# Aux_Board_V5_1.net
KiCad netlist of a schematic drawn in EAGLE
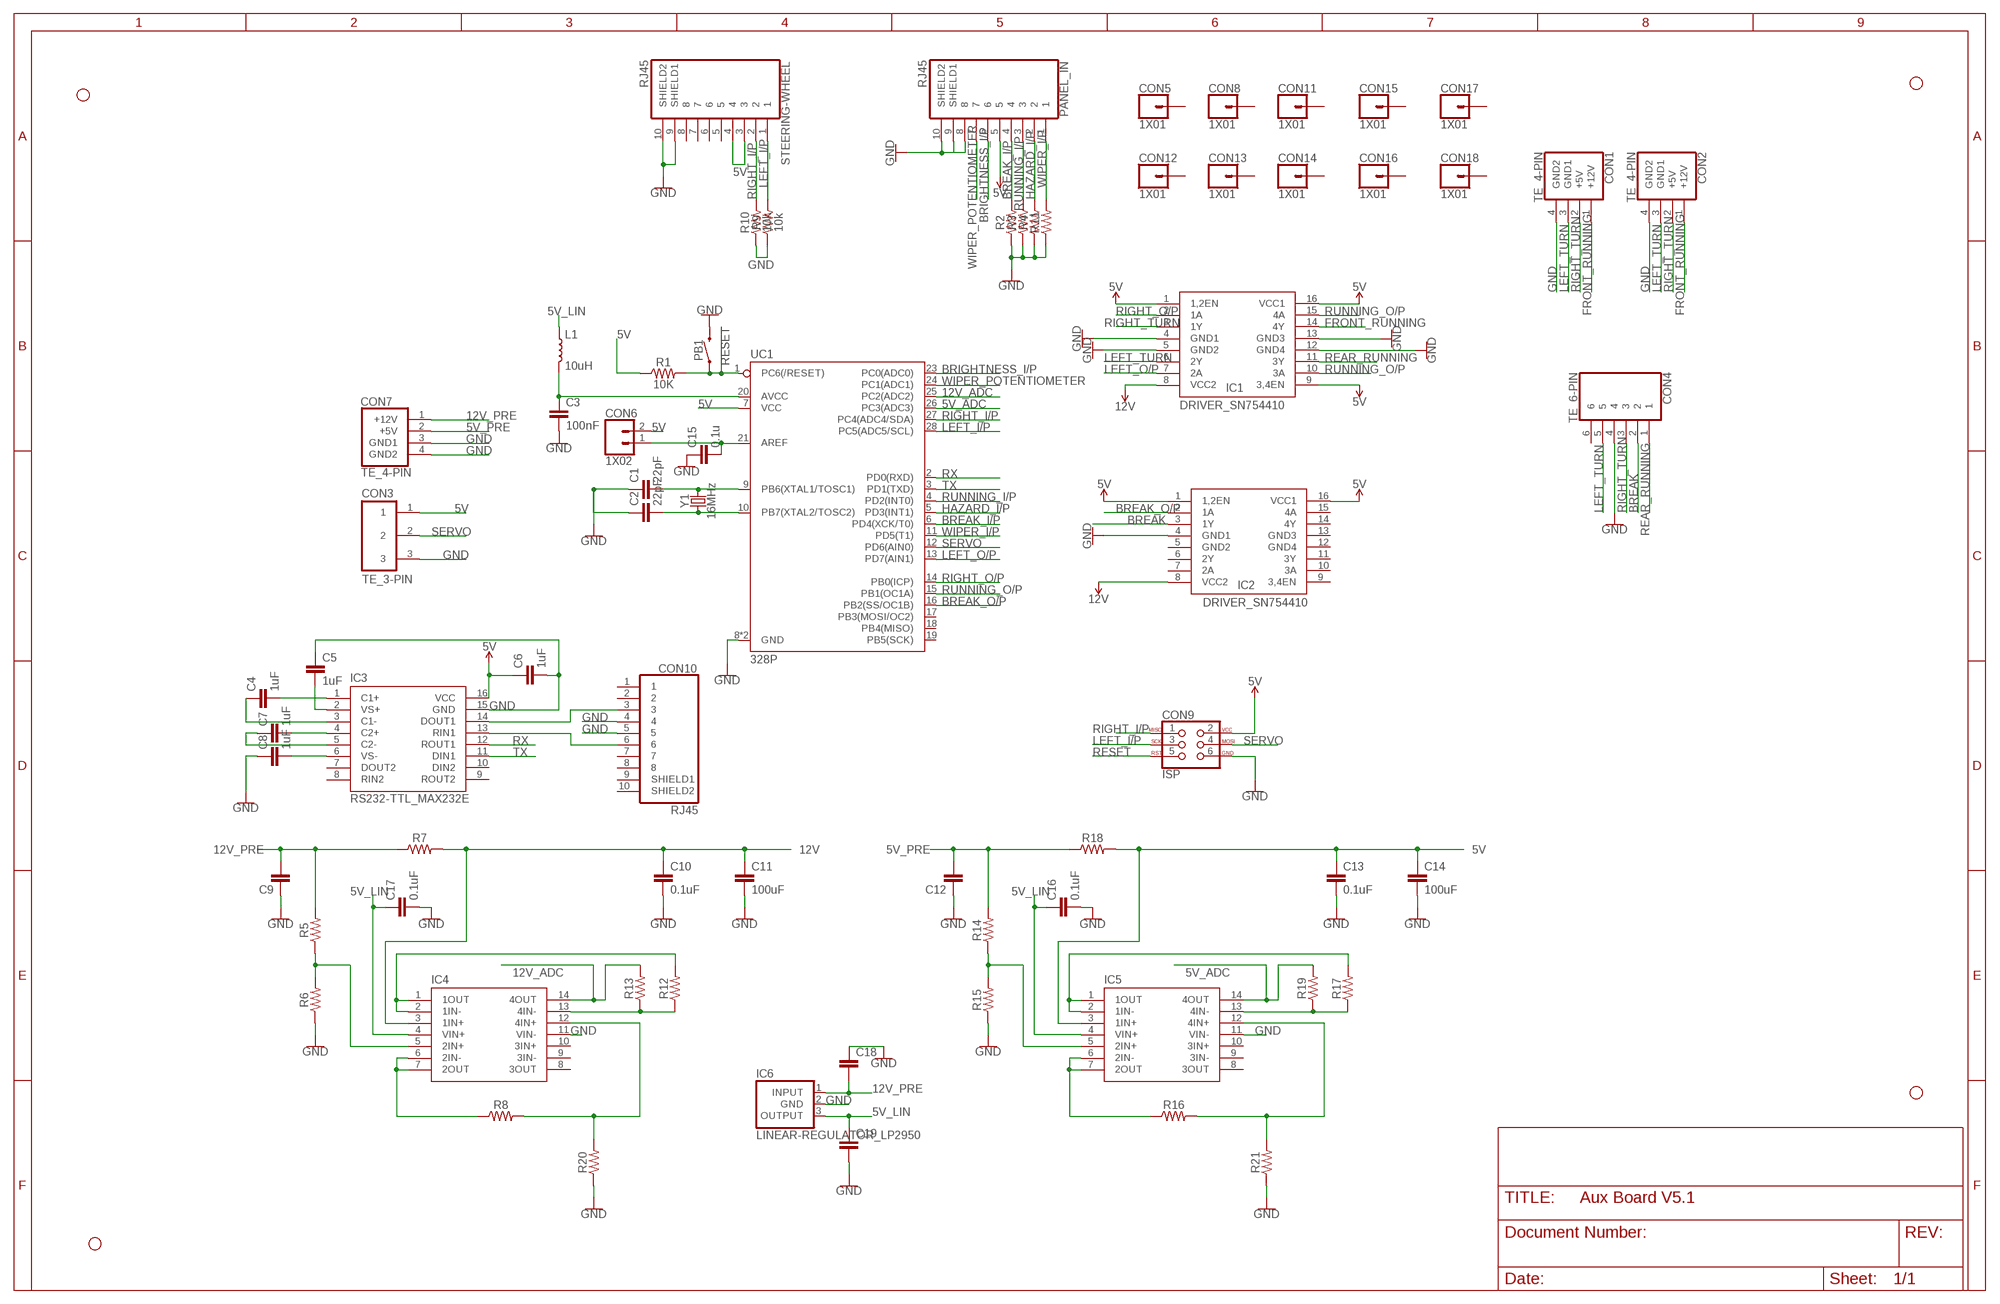
[diagram p0: schematic, sheet 1]

(export (version "E")
  (design (tool "Eeschema 10.0.6"))
  (components
    (comp (ref "C1")
      (value "22pF")
      (footprint "eagle-import:0805")
      (libsource (lib "eagle-import") (part "CAPACITOR_0805"))
    )
    (comp (ref "C2")
      (value "22pF")
      (footprint "eagle-import:0805")
      (libsource (lib "eagle-import") (part "CAPACITOR_0805"))
    )
    (comp (ref "C3")
      (value "100nF")
      (footprint "eagle-import:0805")
      (libsource (lib "eagle-import") (part "CAPACITOR_0805"))
    )
    (comp (ref "C4")
      (value "1uF")
      (footprint "eagle-import:0805")
      (libsource (lib "eagle-import") (part "CAPACITOR_0805"))
    )
    (comp (ref "C5")
      (value "1uF")
      (footprint "eagle-import:0805")
      (libsource (lib "eagle-import") (part "CAPACITOR_0805"))
    )
    (comp (ref "C6")
      (value "1uF")
      (footprint "eagle-import:0805")
      (libsource (lib "eagle-import") (part "CAPACITOR_0805"))
    )
    (comp (ref "C7")
      (value "1uF")
      (footprint "eagle-import:0805")
      (libsource (lib "eagle-import") (part "CAPACITOR_0805"))
    )
    (comp (ref "C8")
      (value "1uF")
      (footprint "eagle-import:0805")
      (libsource (lib "eagle-import") (part "CAPACITOR_0805"))
    )
    (comp (ref "C9")
      (value "CAPACITOR_0805")
      (footprint "eagle-import:0805")
      (libsource (lib "eagle-import") (part "CAPACITOR_0805"))
    )
    (comp (ref "C10")
      (value "0.1uF")
      (footprint "eagle-import:0805")
      (libsource (lib "eagle-import") (part "CAPACITOR_0805"))
    )
    (comp (ref "C11")
      (value "100uF")
      (footprint "eagle-import:0805")
      (libsource (lib "eagle-import") (part "CAPACITOR_0805"))
    )
    (comp (ref "C12")
      (value "CAPACITOR_0805")
      (footprint "eagle-import:0805")
      (libsource (lib "eagle-import") (part "CAPACITOR_0805"))
    )
    (comp (ref "C13")
      (value "0.1uF")
      (footprint "eagle-import:0805")
      (libsource (lib "eagle-import") (part "CAPACITOR_0805"))
    )
    (comp (ref "C14")
      (value "100uF")
      (footprint "eagle-import:0805")
      (libsource (lib "eagle-import") (part "CAPACITOR_0805"))
    )
    (comp (ref "C15")
      (value "0.1u")
      (footprint "eagle-import:0805")
      (libsource (lib "eagle-import") (part "CAPACITOR_0805"))
    )
    (comp (ref "C16")
      (value "0.1uF")
      (footprint "eagle-import:0805")
      (libsource (lib "eagle-import") (part "CAPACITOR_0805"))
    )
    (comp (ref "C17")
      (value "0.1uF")
      (footprint "eagle-import:0805")
      (libsource (lib "eagle-import") (part "CAPACITOR_0805"))
    )
    (comp (ref "C18")
      (value "CAPACITOR_0805")
      (footprint "eagle-import:0805")
      (libsource (lib "eagle-import") (part "CAPACITOR_0805"))
    )
    (comp (ref "C19")
      (value "CAPACITOR_0805")
      (footprint "eagle-import:0805")
      (libsource (lib "eagle-import") (part "CAPACITOR_0805"))
    )
    (comp (ref "CON1")
      (value "TE_4-PIN")
      (footprint "eagle-import:TE_4-PIN")
      (libsource (lib "eagle-import") (part "TE_4-PIN"))
    )
    (comp (ref "CON2")
      (value "TE_4-PIN")
      (footprint "eagle-import:TE_4-PIN")
      (libsource (lib "eagle-import") (part "TE_4-PIN"))
    )
    (comp (ref "CON3")
      (value "TE_3-PIN")
      (footprint "eagle-import:TE_3-PIN")
      (libsource (lib "eagle-import") (part "TE_3-PIN"))
    )
    (comp (ref "CON4")
      (value "TE_6-PIN")
      (footprint "eagle-import:TE_6-PIN")
      (libsource (lib "eagle-import") (part "TE_6-PIN"))
    )
    (comp (ref "CON5")
      (value "1X01")
      (footprint "eagle-import:1X01")
      (libsource (lib "eagle-import") (part "1X01"))
    )
    (comp (ref "CON6")
      (value "1X02")
      (footprint "eagle-import:1X02")
      (libsource (lib "eagle-import") (part "1X02"))
    )
    (comp (ref "CON7")
      (value "TE_4-PIN")
      (footprint "eagle-import:TE_4-PIN")
      (libsource (lib "eagle-import") (part "TE_4-PIN"))
    )
    (comp (ref "CON8")
      (value "1X01")
      (footprint "eagle-import:1X01")
      (libsource (lib "eagle-import") (part "1X01"))
    )
    (comp (ref "CON9")
      (value "ISP")
      (footprint "eagle-import:ISP_CONNECTOR")
      (libsource (lib "eagle-import") (part "ISP"))
    )
    (comp (ref "CON10")
      (value "RJ45")
      (footprint "eagle-import:RJ45")
      (libsource (lib "eagle-import") (part "RJ45"))
    )
    (comp (ref "CON11")
      (value "1X01")
      (footprint "eagle-import:1X01")
      (libsource (lib "eagle-import") (part "1X01"))
    )
    (comp (ref "CON12")
      (value "1X01")
      (footprint "eagle-import:1X01")
      (libsource (lib "eagle-import") (part "1X01"))
    )
    (comp (ref "CON13")
      (value "1X01")
      (footprint "eagle-import:1X01")
      (libsource (lib "eagle-import") (part "1X01"))
    )
    (comp (ref "CON14")
      (value "1X01")
      (footprint "eagle-import:1X01")
      (libsource (lib "eagle-import") (part "1X01"))
    )
    (comp (ref "CON15")
      (value "1X01")
      (footprint "eagle-import:1X01")
      (libsource (lib "eagle-import") (part "1X01"))
    )
    (comp (ref "CON16")
      (value "1X01")
      (footprint "eagle-import:1X01")
      (libsource (lib "eagle-import") (part "1X01"))
    )
    (comp (ref "CON17")
      (value "1X01")
      (footprint "eagle-import:1X01")
      (libsource (lib "eagle-import") (part "1X01"))
    )
    (comp (ref "CON18")
      (value "1X01")
      (footprint "eagle-import:1X01")
      (libsource (lib "eagle-import") (part "1X01"))
    )
    (comp (ref "H1")
      (value "STAND-OFF")
      (footprint "eagle-import:STAND-OFF")
      (libsource (lib "eagle-import") (part "STAND-OFF"))
    )
    (comp (ref "H2")
      (value "STAND-OFF")
      (footprint "eagle-import:STAND-OFF")
      (libsource (lib "eagle-import") (part "STAND-OFF"))
    )
    (comp (ref "H3")
      (value "STAND-OFF")
      (footprint "eagle-import:STAND-OFF")
      (libsource (lib "eagle-import") (part "STAND-OFF"))
    )
    (comp (ref "H4")
      (value "STAND-OFF")
      (footprint "eagle-import:STAND-OFF")
      (libsource (lib "eagle-import") (part "STAND-OFF"))
    )
    (comp (ref "IC1")
      (value "DRIVER_SN754410")
      (footprint "eagle-import:DIP16")
      (libsource (lib "eagle-import") (part "DRIVER_SN754410"))
    )
    (comp (ref "IC2")
      (value "DRIVER_SN754410")
      (footprint "eagle-import:DIP16")
      (libsource (lib "eagle-import") (part "DRIVER_SN754410"))
    )
    (comp (ref "IC3")
      (value "RS232-TTL_MAX232E")
      (footprint "eagle-import:DIP16")
      (libsource (lib "eagle-import") (part "RS232-TTL_MAX232E"))
    )
    (comp (ref "IC4")
      (value "OP-AMP_QUAD")
      (footprint "eagle-import:DIP14")
      (libsource (lib "eagle-import") (part "OP-AMP_QUAD"))
    )
    (comp (ref "IC5")
      (value "OP-AMP_QUAD")
      (footprint "eagle-import:DIP14")
      (libsource (lib "eagle-import") (part "OP-AMP_QUAD"))
    )
    (comp (ref "IC6")
      (value "LINEAR-REGULATOR_LP2950")
      (footprint "eagle-import:TO92")
      (libsource (lib "eagle-import") (part "LINEAR-REGULATOR_LP2950"))
    )
    (comp (ref "L1")
      (value "10uH")
      (footprint "eagle-import:0805")
      (libsource (lib "eagle-import") (part "INDUCTOR_0805"))
    )
    (comp (ref "PANEL_IN")
      (value "RJ45")
      (footprint "eagle-import:RJ45")
      (libsource (lib "eagle-import") (part "RJ45"))
    )
    (comp (ref "PB1")
      (value "PUSHBUTTON")
      (footprint "eagle-import:PUSHBUTTON")
      (libsource (lib "eagle-import") (part "PUSHBUTTON"))
    )
    (comp (ref "R1")
      (value "10K")
      (footprint "eagle-import:0805")
      (libsource (lib "eagle-import") (part "RESISTOR_0805"))
    )
    (comp (ref "R2")
      (value "RESISTOR_0805")
      (footprint "eagle-import:0805")
      (libsource (lib "eagle-import") (part "RESISTOR_0805"))
    )
    (comp (ref "R3")
      (value "RESISTOR_0805")
      (footprint "eagle-import:0805")
      (libsource (lib "eagle-import") (part "RESISTOR_0805"))
    )
    (comp (ref "R4")
      (value "RESISTOR_0805")
      (footprint "eagle-import:0805")
      (libsource (lib "eagle-import") (part "RESISTOR_0805"))
    )
    (comp (ref "R5")
      (value "RESISTOR_0805")
      (footprint "eagle-import:0805")
      (libsource (lib "eagle-import") (part "RESISTOR_0805"))
    )
    (comp (ref "R6")
      (value "RESISTOR_0805")
      (footprint "eagle-import:0805")
      (libsource (lib "eagle-import") (part "RESISTOR_0805"))
    )
    (comp (ref "R7")
      (value "RESISTOR_1210")
      (footprint "eagle-import:1210")
      (libsource (lib "eagle-import") (part "RESISTOR_1210"))
    )
    (comp (ref "R8")
      (value "RESISTOR_0805")
      (footprint "eagle-import:0805")
      (libsource (lib "eagle-import") (part "RESISTOR_0805"))
    )
    (comp (ref "R9")
      (value "10k")
      (footprint "eagle-import:0805")
      (libsource (lib "eagle-import") (part "RESISTOR_0805"))
    )
    (comp (ref "R10")
      (value "10k")
      (footprint "eagle-import:0805")
      (libsource (lib "eagle-import") (part "RESISTOR_0805"))
    )
    (comp (ref "R11")
      (value "RESISTOR_0805")
      (footprint "eagle-import:0805")
      (libsource (lib "eagle-import") (part "RESISTOR_0805"))
    )
    (comp (ref "R12")
      (value "RESISTOR_0805")
      (footprint "eagle-import:0805")
      (libsource (lib "eagle-import") (part "RESISTOR_0805"))
    )
    (comp (ref "R13")
      (value "RESISTOR_0805")
      (footprint "eagle-import:0805")
      (libsource (lib "eagle-import") (part "RESISTOR_0805"))
    )
    (comp (ref "R14")
      (value "RESISTOR_0805")
      (footprint "eagle-import:0805")
      (libsource (lib "eagle-import") (part "RESISTOR_0805"))
    )
    (comp (ref "R15")
      (value "RESISTOR_0805")
      (footprint "eagle-import:0805")
      (libsource (lib "eagle-import") (part "RESISTOR_0805"))
    )
    (comp (ref "R16")
      (value "RESISTOR_0805")
      (footprint "eagle-import:0805")
      (libsource (lib "eagle-import") (part "RESISTOR_0805"))
    )
    (comp (ref "R17")
      (value "RESISTOR_0805")
      (footprint "eagle-import:0805")
      (libsource (lib "eagle-import") (part "RESISTOR_0805"))
    )
    (comp (ref "R18")
      (value "RESISTOR_1210")
      (footprint "eagle-import:1210")
      (libsource (lib "eagle-import") (part "RESISTOR_1210"))
    )
    (comp (ref "R19")
      (value "RESISTOR_0805")
      (footprint "eagle-import:0805")
      (libsource (lib "eagle-import") (part "RESISTOR_0805"))
    )
    (comp (ref "R20")
      (value "RESISTOR_0805")
      (footprint "eagle-import:0805")
      (libsource (lib "eagle-import") (part "RESISTOR_0805"))
    )
    (comp (ref "R21")
      (value "RESISTOR_0805")
      (footprint "eagle-import:0805")
      (libsource (lib "eagle-import") (part "RESISTOR_0805"))
    )
    (comp (ref "STEERING-WHEEL")
      (value "RJ45")
      (footprint "eagle-import:RJ45")
      (libsource (lib "eagle-import") (part "RJ45"))
    )
    (comp (ref "UC1")
      (value "328P")
      (footprint "eagle-import:DIP28")
      (libsource (lib "eagle-import") (part "ATMEGA328P_DIP28"))
    )
    (comp (ref "Y1")
      (value "16MHz")
      (footprint "eagle-import:HC49US")
      (libsource (lib "eagle-import") (part "CRYSTAL-16MHZPTH-HC49US"))
    )
  )
  (nets
    (net (code "1") (name "/5V_ADC") (class "Default")
      (node (ref "IC5") (pin "14") (pinfunction "4OUT_14") (pintype "bidirectional"))
      (node (ref "R19") (pin "2") (pinfunction "2_2") (pintype "passive"))
      (node (ref "UC1") (pin "26") (pinfunction "PC3(ADC3)_26") (pintype "bidirectional"))
    )
    (net (code "2") (name "/5V_LIN") (class "Default")
      (node (ref "C16") (pin "1") (pinfunction "1_1") (pintype "passive"))
      (node (ref "C17") (pin "1") (pinfunction "1_1") (pintype "passive"))
      (node (ref "C19") (pin "1") (pinfunction "1_1") (pintype "passive"))
      (node (ref "IC4") (pin "4") (pinfunction "VIN+_4") (pintype "bidirectional"))
      (node (ref "IC5") (pin "4") (pinfunction "VIN+_4") (pintype "bidirectional"))
      (node (ref "IC6") (pin "3") (pinfunction "OUTPUT_3") (pintype "bidirectional"))
      (node (ref "L1") (pin "1") (pinfunction "1_1") (pintype "passive"))
    )
    (net (code "3") (name "/5V_PRE") (class "Default")
      (node (ref "C12") (pin "2") (pinfunction "2_2") (pintype "passive"))
      (node (ref "CON7") (pin "2") (pinfunction "+5V_2") (pintype "passive"))
      (node (ref "R14") (pin "2") (pinfunction "2_2") (pintype "passive"))
      (node (ref "R18") (pin "1") (pinfunction "1_1") (pintype "passive"))
    )
    (net (code "4") (name "/12V_ADC") (class "Default")
      (node (ref "IC4") (pin "14") (pinfunction "4OUT_14") (pintype "bidirectional"))
      (node (ref "R13") (pin "2") (pinfunction "2_2") (pintype "passive"))
      (node (ref "UC1") (pin "25") (pinfunction "PC2(ADC2)_25") (pintype "bidirectional"))
    )
    (net (code "5") (name "/12V_PRE") (class "Default")
      (node (ref "C18") (pin "2") (pinfunction "2_2") (pintype "passive"))
      (node (ref "C9") (pin "2") (pinfunction "2_2") (pintype "passive"))
      (node (ref "CON7") (pin "1") (pinfunction "+12V_1") (pintype "passive"))
      (node (ref "IC6") (pin "1") (pinfunction "INPUT_1") (pintype "bidirectional"))
      (node (ref "R5") (pin "2") (pinfunction "2_2") (pintype "passive"))
      (node (ref "R7") (pin "1") (pinfunction "1_1") (pintype "passive"))
    )
    (net (code "6") (name "/BREAK") (class "Default")
      (node (ref "CON4") (pin "2") (pinfunction "2_2") (pintype "passive"))
      (node (ref "IC2") (pin "3") (pinfunction "1Y_3") (pintype "bidirectional"))
    )
    (net (code "7") (name "/BREAK_I{slash}P") (class "Default")
      (node (ref "PANEL_IN") (pin "4") (pinfunction "4_4") (pintype "passive"))
      (node (ref "R2") (pin "2") (pinfunction "2_2") (pintype "passive"))
      (node (ref "UC1") (pin "6") (pinfunction "PD4(XCK/T0)_6") (pintype "bidirectional"))
    )
    (net (code "8") (name "/BREAK_O{slash}P") (class "Default")
      (node (ref "IC2") (pin "2") (pinfunction "1A_2") (pintype "bidirectional"))
      (node (ref "UC1") (pin "16") (pinfunction "PB2(SS/OC1B)_16") (pintype "bidirectional"))
    )
    (net (code "9") (name "/BRIGHTNESS_I{slash}P") (class "Default")
      (node (ref "PANEL_IN") (pin "6") (pinfunction "6_6") (pintype "passive"))
      (node (ref "UC1") (pin "23") (pinfunction "PC0(ADC0)_23") (pintype "bidirectional"))
    )
    (net (code "10") (name "/FRONT_RUNNING") (class "Default")
      (node (ref "CON1") (pin "1") (pinfunction "+12V_1") (pintype "passive"))
      (node (ref "CON2") (pin "1") (pinfunction "+12V_1") (pintype "passive"))
      (node (ref "IC1") (pin "14") (pinfunction "4Y_14") (pintype "bidirectional"))
    )
    (net (code "11") (name "/HAZARD_I{slash}P") (class "Default")
      (node (ref "PANEL_IN") (pin "2") (pinfunction "2_2") (pintype "passive"))
      (node (ref "R4") (pin "2") (pinfunction "2_2") (pintype "passive"))
      (node (ref "UC1") (pin "5") (pinfunction "PD3(INT1)_5") (pintype "bidirectional"))
    )
    (net (code "12") (name "/LEFT_I{slash}P") (class "Default")
      (node (ref "CON9") (pin "3") (pinfunction "3_3") (pintype "passive"))
      (node (ref "R9") (pin "2") (pinfunction "2_2") (pintype "passive"))
      (node (ref "STEERING-WHEEL") (pin "1") (pinfunction "1_1") (pintype "passive"))
      (node (ref "UC1") (pin "28") (pinfunction "PC5(ADC5/SCL)_28") (pintype "bidirectional"))
    )
    (net (code "13") (name "/LEFT_O{slash}P") (class "Default")
      (node (ref "IC1") (pin "7") (pinfunction "2A_7") (pintype "bidirectional"))
      (node (ref "UC1") (pin "13") (pinfunction "PD7(AIN1)_13") (pintype "bidirectional"))
    )
    (net (code "14") (name "/LEFT_TURN") (class "Default")
      (node (ref "CON1") (pin "3") (pinfunction "GND1_3") (pintype "passive"))
      (node (ref "CON2") (pin "3") (pinfunction "GND1_3") (pintype "passive"))
      (node (ref "CON4") (pin "5") (pinfunction "5_5") (pintype "passive"))
      (node (ref "IC1") (pin "6") (pinfunction "2Y_6") (pintype "bidirectional"))
    )
    (net (code "15") (name "/REAR_RUNNING") (class "Default")
      (node (ref "CON4") (pin "1") (pinfunction "1_1") (pintype "passive"))
      (node (ref "IC1") (pin "11") (pinfunction "3Y_11") (pintype "bidirectional"))
    )
    (net (code "16") (name "/RESET") (class "Default")
      (node (ref "CON9") (pin "5") (pinfunction "5_5") (pintype "passive"))
      (node (ref "PB1") (pin "1") (pinfunction "1_1") (pintype "passive"))
      (node (ref "PB1") (pin "2") (pinfunction "1_2") (pintype "passive"))
      (node (ref "R1") (pin "2") (pinfunction "2_2") (pintype "passive"))
      (node (ref "UC1") (pin "1") (pinfunction "PC6(/RESET)_1") (pintype "bidirectional"))
    )
    (net (code "17") (name "/RIGHT_I{slash}P") (class "Default")
      (node (ref "CON9") (pin "1") (pinfunction "1_1") (pintype "passive"))
      (node (ref "R10") (pin "2") (pinfunction "2_2") (pintype "passive"))
      (node (ref "STEERING-WHEEL") (pin "2") (pinfunction "2_2") (pintype "passive"))
      (node (ref "UC1") (pin "27") (pinfunction "PC4(ADC4/SDA)_27") (pintype "bidirectional"))
    )
    (net (code "18") (name "/RIGHT_O{slash}P") (class "Default")
      (node (ref "IC1") (pin "2") (pinfunction "1A_2") (pintype "bidirectional"))
      (node (ref "UC1") (pin "14") (pinfunction "PB0(ICP)_14") (pintype "bidirectional"))
    )
    (net (code "19") (name "/RIGHT_TURN") (class "Default")
      (node (ref "CON1") (pin "2") (pinfunction "+5V_2") (pintype "passive"))
      (node (ref "CON2") (pin "2") (pinfunction "+5V_2") (pintype "passive"))
      (node (ref "CON4") (pin "3") (pinfunction "3_3") (pintype "passive"))
      (node (ref "IC1") (pin "3") (pinfunction "1Y_3") (pintype "bidirectional"))
    )
    (net (code "20") (name "/RUNNING_I{slash}P") (class "Default")
      (node (ref "PANEL_IN") (pin "3") (pinfunction "3_3") (pintype "passive"))
      (node (ref "R3") (pin "2") (pinfunction "2_2") (pintype "passive"))
      (node (ref "UC1") (pin "4") (pinfunction "PD2(INT0)_4") (pintype "bidirectional"))
    )
    (net (code "21") (name "/RUNNING_O{slash}P") (class "Default")
      (node (ref "IC1") (pin "10") (pinfunction "3A_10") (pintype "bidirectional"))
      (node (ref "IC1") (pin "15") (pinfunction "4A_15") (pintype "bidirectional"))
      (node (ref "UC1") (pin "15") (pinfunction "PB1(OC1A)_15") (pintype "bidirectional"))
    )
    (net (code "22") (name "/RX") (class "Default")
      (node (ref "IC3") (pin "12") (pinfunction "ROUT1_12") (pintype "bidirectional"))
      (node (ref "UC1") (pin "2") (pinfunction "PD0(RXD)_2") (pintype "bidirectional"))
    )
    (net (code "23") (name "/SERVO") (class "Default")
      (node (ref "CON3") (pin "2") (pinfunction "2_2") (pintype "passive"))
      (node (ref "CON9") (pin "4") (pinfunction "4_4") (pintype "passive"))
      (node (ref "UC1") (pin "12") (pinfunction "PD6(AIN0)_12") (pintype "bidirectional"))
    )
    (net (code "24") (name "/TX") (class "Default")
      (node (ref "IC3") (pin "11") (pinfunction "DIN1_11") (pintype "bidirectional"))
      (node (ref "UC1") (pin "3") (pinfunction "PD1(TXD)_3") (pintype "bidirectional"))
    )
    (net (code "25") (name "/WIPER_I{slash}P") (class "Default")
      (node (ref "PANEL_IN") (pin "1") (pinfunction "1_1") (pintype "passive"))
      (node (ref "R11") (pin "2") (pinfunction "2_2") (pintype "passive"))
      (node (ref "UC1") (pin "11") (pinfunction "PD5(T1)_11") (pintype "bidirectional"))
    )
    (net (code "26") (name "/WIPER_POTENTIOMETER") (class "Default")
      (node (ref "PANEL_IN") (pin "7") (pinfunction "7_7") (pintype "passive"))
      (node (ref "UC1") (pin "24") (pinfunction "PC1(ADC1)_24") (pintype "bidirectional"))
    )
    (net (code "27") (name "5V") (class "Default")
      (node (ref "C13") (pin "1") (pinfunction "1_1") (pintype "passive"))
      (node (ref "C14") (pin "1") (pinfunction "1_1") (pintype "passive"))
      (node (ref "C15") (pin "2") (pinfunction "2_2") (pintype "passive"))
      (node (ref "C6") (pin "1") (pinfunction "1_1") (pintype "passive"))
      (node (ref "CON3") (pin "1") (pinfunction "1_1") (pintype "passive"))
      (node (ref "CON6") (pin "1") (pinfunction "1_1") (pintype "passive"))
      (node (ref "CON6") (pin "2") (pinfunction "2_2") (pintype "passive"))
      (node (ref "CON9") (pin "2") (pinfunction "2_2") (pintype "passive"))
      (node (ref "IC1") (pin "1") (pinfunction "1,2EN_1") (pintype "bidirectional"))
      (node (ref "IC1") (pin "16") (pinfunction "VCC1_16") (pintype "bidirectional"))
      (node (ref "IC1") (pin "9") (pinfunction "3,4EN_9") (pintype "bidirectional"))
      (node (ref "IC2") (pin "1") (pinfunction "1,2EN_1") (pintype "bidirectional"))
      (node (ref "IC2") (pin "16") (pinfunction "VCC1_16") (pintype "bidirectional"))
      (node (ref "IC3") (pin "16") (pinfunction "VCC_16") (pintype "bidirectional"))
      (node (ref "IC5") (pin "3") (pinfunction "1IN+_3") (pintype "bidirectional"))
      (node (ref "PANEL_IN") (pin "5") (pinfunction "5_5") (pintype "passive"))
      (node (ref "R1") (pin "1") (pinfunction "1_1") (pintype "passive"))
      (node (ref "R18") (pin "2") (pinfunction "2_2") (pintype "passive"))
      (node (ref "STEERING-WHEEL") (pin "3") (pinfunction "3_3") (pintype "passive"))
      (node (ref "STEERING-WHEEL") (pin "4") (pinfunction "4_4") (pintype "passive"))
      (node (ref "UC1") (pin "21") (pinfunction "AREF_21") (pintype "bidirectional"))
      (node (ref "UC1") (pin "7") (pinfunction "VCC_7") (pintype "bidirectional"))
    )
    (net (code "28") (name "12V") (class "Default")
      (node (ref "C10") (pin "1") (pinfunction "1_1") (pintype "passive"))
      (node (ref "C11") (pin "1") (pinfunction "1_1") (pintype "passive"))
      (node (ref "IC1") (pin "8") (pinfunction "VCC2_8") (pintype "bidirectional"))
      (node (ref "IC2") (pin "8") (pinfunction "VCC2_8") (pintype "bidirectional"))
      (node (ref "IC4") (pin "3") (pinfunction "1IN+_3") (pintype "bidirectional"))
      (node (ref "R7") (pin "2") (pinfunction "2_2") (pintype "passive"))
    )
    (net (code "29") (name "GND") (class "Default")
      (node (ref "C1") (pin "1") (pinfunction "1_1") (pintype "passive"))
      (node (ref "C10") (pin "2") (pinfunction "2_2") (pintype "passive"))
      (node (ref "C11") (pin "2") (pinfunction "2_2") (pintype "passive"))
      (node (ref "C12") (pin "1") (pinfunction "1_1") (pintype "passive"))
      (node (ref "C13") (pin "2") (pinfunction "2_2") (pintype "passive"))
      (node (ref "C14") (pin "2") (pinfunction "2_2") (pintype "passive"))
      (node (ref "C15") (pin "1") (pinfunction "1_1") (pintype "passive"))
      (node (ref "C16") (pin "2") (pinfunction "2_2") (pintype "passive"))
      (node (ref "C17") (pin "2") (pinfunction "2_2") (pintype "passive"))
      (node (ref "C18") (pin "1") (pinfunction "1_1") (pintype "passive"))
      (node (ref "C19") (pin "2") (pinfunction "2_2") (pintype "passive"))
      (node (ref "C2") (pin "1") (pinfunction "1_1") (pintype "passive"))
      (node (ref "C3") (pin "2") (pinfunction "2_2") (pintype "passive"))
      (node (ref "C5") (pin "1") (pinfunction "1_1") (pintype "passive"))
      (node (ref "C6") (pin "2") (pinfunction "2_2") (pintype "passive"))
      (node (ref "C8") (pin "1") (pinfunction "1_1") (pintype "passive"))
      (node (ref "C9") (pin "1") (pinfunction "1_1") (pintype "passive"))
      (node (ref "CON1") (pin "4") (pinfunction "GND2_4") (pintype "passive"))
      (node (ref "CON10") (pin "4") (pinfunction "4_4") (pintype "passive"))
      (node (ref "CON10") (pin "5") (pinfunction "5_5") (pintype "passive"))
      (node (ref "CON2") (pin "4") (pinfunction "GND2_4") (pintype "passive"))
      (node (ref "CON3") (pin "3") (pinfunction "3_3") (pintype "passive"))
      (node (ref "CON4") (pin "4") (pinfunction "4_4") (pintype "passive"))
      (node (ref "CON7") (pin "3") (pinfunction "GND1_3") (pintype "passive"))
      (node (ref "CON7") (pin "4") (pinfunction "GND2_4") (pintype "passive"))
      (node (ref "CON9") (pin "6") (pinfunction "6_6") (pintype "passive"))
      (node (ref "IC1") (pin "12") (pinfunction "GND4_12") (pintype "bidirectional"))
      (node (ref "IC1") (pin "13") (pinfunction "GND3_13") (pintype "bidirectional"))
      (node (ref "IC1") (pin "4") (pinfunction "GND1_4") (pintype "bidirectional"))
      (node (ref "IC1") (pin "5") (pinfunction "GND2_5") (pintype "bidirectional"))
      (node (ref "IC2") (pin "4") (pinfunction "GND1_4") (pintype "bidirectional"))
      (node (ref "IC3") (pin "15") (pinfunction "GND_15") (pintype "bidirectional"))
      (node (ref "IC4") (pin "11") (pinfunction "VIN-_11") (pintype "bidirectional"))
      (node (ref "IC5") (pin "11") (pinfunction "VIN-_11") (pintype "bidirectional"))
      (node (ref "IC6") (pin "2") (pinfunction "GND_2") (pintype "bidirectional"))
      (node (ref "PANEL_IN") (pin "10") (pinfunction "SHIELD2_10") (pintype "passive"))
      (node (ref "PANEL_IN") (pin "8") (pinfunction "8_8") (pintype "passive"))
      (node (ref "PANEL_IN") (pin "9") (pinfunction "SHIELD1_9") (pintype "passive"))
      (node (ref "PB1") (pin "3") (pinfunction "2_3") (pintype "passive"))
      (node (ref "PB1") (pin "4") (pinfunction "2_4") (pintype "passive"))
      (node (ref "R10") (pin "1") (pinfunction "1_1") (pintype "passive"))
      (node (ref "R11") (pin "1") (pinfunction "1_1") (pintype "passive"))
      (node (ref "R15") (pin "1") (pinfunction "1_1") (pintype "passive"))
      (node (ref "R2") (pin "1") (pinfunction "1_1") (pintype "passive"))
      (node (ref "R20") (pin "1") (pinfunction "1_1") (pintype "passive"))
      (node (ref "R21") (pin "1") (pinfunction "1_1") (pintype "passive"))
      (node (ref "R3") (pin "1") (pinfunction "1_1") (pintype "passive"))
      (node (ref "R4") (pin "1") (pinfunction "1_1") (pintype "passive"))
      (node (ref "R6") (pin "1") (pinfunction "1_1") (pintype "passive"))
      (node (ref "R9") (pin "1") (pinfunction "1_1") (pintype "passive"))
      (node (ref "STEERING-WHEEL") (pin "10") (pinfunction "SHIELD2_10") (pintype "passive"))
      (node (ref "STEERING-WHEEL") (pin "9") (pinfunction "SHIELD1_9") (pintype "passive"))
      (node (ref "UC1") (pin "22") (pinfunction "GND_22") (pintype "bidirectional"))
      (node (ref "UC1") (pin "8") (pinfunction "GND_8") (pintype "bidirectional"))
    )
    (net (code "30") (name "Net-(IC3-C1+)") (class "Default")
      (node (ref "C4") (pin "2") (pinfunction "2_2") (pintype "passive"))
      (node (ref "IC3") (pin "1") (pinfunction "C1+_1") (pintype "bidirectional"))
    )
    (net (code "31") (name "Net-(IC3-C1-)") (class "Default")
      (node (ref "C4") (pin "1") (pinfunction "1_1") (pintype "passive"))
      (node (ref "IC3") (pin "3") (pinfunction "C1-_3") (pintype "bidirectional"))
    )
    (net (code "32") (name "Net-(IC3-C2+)") (class "Default")
      (node (ref "C7") (pin "2") (pinfunction "2_2") (pintype "passive"))
      (node (ref "IC3") (pin "4") (pinfunction "C2+_4") (pintype "bidirectional"))
    )
    (net (code "33") (name "Net-(IC3-C2-)") (class "Default")
      (node (ref "C7") (pin "1") (pinfunction "1_1") (pintype "passive"))
      (node (ref "IC3") (pin "5") (pinfunction "C2-_5") (pintype "bidirectional"))
    )
    (net (code "34") (name "Net-(IC3-DOUT1)") (class "Default")
      (node (ref "CON10") (pin "3") (pinfunction "3_3") (pintype "passive"))
      (node (ref "IC3") (pin "14") (pinfunction "DOUT1_14") (pintype "bidirectional"))
    )
    (net (code "35") (name "Net-(IC3-RIN1)") (class "Default")
      (node (ref "CON10") (pin "6") (pinfunction "6_6") (pintype "passive"))
      (node (ref "IC3") (pin "13") (pinfunction "RIN1_13") (pintype "bidirectional"))
    )
    (net (code "36") (name "Net-(IC3-VS+)") (class "Default")
      (node (ref "C5") (pin "2") (pinfunction "2_2") (pintype "passive"))
      (node (ref "IC3") (pin "2") (pinfunction "VS+_2") (pintype "bidirectional"))
    )
    (net (code "37") (name "Net-(IC3-VS-)") (class "Default")
      (node (ref "C8") (pin "2") (pinfunction "2_2") (pintype "passive"))
      (node (ref "IC3") (pin "6") (pinfunction "VS-_6") (pintype "bidirectional"))
    )
    (net (code "38") (name "Net-(IC4-1IN-)") (class "Default")
      (node (ref "IC4") (pin "1") (pinfunction "1OUT_1") (pintype "bidirectional"))
      (node (ref "IC4") (pin "2") (pinfunction "1IN-_2") (pintype "bidirectional"))
      (node (ref "R12") (pin "2") (pinfunction "2_2") (pintype "passive"))
    )
    (net (code "39") (name "Net-(IC4-2IN+)") (class "Default")
      (node (ref "IC4") (pin "5") (pinfunction "2IN+_5") (pintype "bidirectional"))
      (node (ref "R5") (pin "1") (pinfunction "1_1") (pintype "passive"))
      (node (ref "R6") (pin "2") (pinfunction "2_2") (pintype "passive"))
    )
    (net (code "40") (name "Net-(IC4-2IN-)") (class "Default")
      (node (ref "IC4") (pin "6") (pinfunction "2IN-_6") (pintype "bidirectional"))
      (node (ref "IC4") (pin "7") (pinfunction "2OUT_7") (pintype "bidirectional"))
      (node (ref "R8") (pin "1") (pinfunction "1_1") (pintype "passive"))
    )
    (net (code "41") (name "Net-(IC4-4IN+)") (class "Default")
      (node (ref "IC4") (pin "12") (pinfunction "4IN+_12") (pintype "bidirectional"))
      (node (ref "R20") (pin "2") (pinfunction "2_2") (pintype "passive"))
      (node (ref "R8") (pin "2") (pinfunction "2_2") (pintype "passive"))
    )
    (net (code "42") (name "Net-(IC4-4IN-)") (class "Default")
      (node (ref "IC4") (pin "13") (pinfunction "4IN-_13") (pintype "bidirectional"))
      (node (ref "R12") (pin "1") (pinfunction "1_1") (pintype "passive"))
      (node (ref "R13") (pin "1") (pinfunction "1_1") (pintype "passive"))
    )
    (net (code "43") (name "Net-(IC5-1IN-)") (class "Default")
      (node (ref "IC5") (pin "1") (pinfunction "1OUT_1") (pintype "bidirectional"))
      (node (ref "IC5") (pin "2") (pinfunction "1IN-_2") (pintype "bidirectional"))
      (node (ref "R17") (pin "2") (pinfunction "2_2") (pintype "passive"))
    )
    (net (code "44") (name "Net-(IC5-2IN+)") (class "Default")
      (node (ref "IC5") (pin "5") (pinfunction "2IN+_5") (pintype "bidirectional"))
      (node (ref "R14") (pin "1") (pinfunction "1_1") (pintype "passive"))
      (node (ref "R15") (pin "2") (pinfunction "2_2") (pintype "passive"))
    )
    (net (code "45") (name "Net-(IC5-2IN-)") (class "Default")
      (node (ref "IC5") (pin "6") (pinfunction "2IN-_6") (pintype "bidirectional"))
      (node (ref "IC5") (pin "7") (pinfunction "2OUT_7") (pintype "bidirectional"))
      (node (ref "R16") (pin "1") (pinfunction "1_1") (pintype "passive"))
    )
    (net (code "46") (name "Net-(IC5-4IN+)") (class "Default")
      (node (ref "IC5") (pin "12") (pinfunction "4IN+_12") (pintype "bidirectional"))
      (node (ref "R16") (pin "2") (pinfunction "2_2") (pintype "passive"))
      (node (ref "R21") (pin "2") (pinfunction "2_2") (pintype "passive"))
    )
    (net (code "47") (name "Net-(IC5-4IN-)") (class "Default")
      (node (ref "IC5") (pin "13") (pinfunction "4IN-_13") (pintype "bidirectional"))
      (node (ref "R17") (pin "1") (pinfunction "1_1") (pintype "passive"))
      (node (ref "R19") (pin "1") (pinfunction "1_1") (pintype "passive"))
    )
    (net (code "48") (name "Net-(UC1-AVCC)") (class "Default")
      (node (ref "C3") (pin "1") (pinfunction "1_1") (pintype "passive"))
      (node (ref "L1") (pin "2") (pinfunction "2_2") (pintype "passive"))
      (node (ref "UC1") (pin "20") (pinfunction "AVCC_20") (pintype "bidirectional"))
    )
    (net (code "49") (name "Net-(UC1-PB6(XTAL1{slash}TOSC1))") (class "Default")
      (node (ref "C1") (pin "2") (pinfunction "2_2") (pintype "passive"))
      (node (ref "UC1") (pin "9") (pinfunction "PB6(XTAL1/TOSC1)_9") (pintype "bidirectional"))
      (node (ref "Y1") (pin "2") (pinfunction "2_2") (pintype "passive"))
    )
    (net (code "50") (name "Net-(UC1-PB7(XTAL2{slash}TOSC2))") (class "Default")
      (node (ref "C2") (pin "2") (pinfunction "2_2") (pintype "passive"))
      (node (ref "UC1") (pin "10") (pinfunction "PB7(XTAL2/TOSC2)_10") (pintype "bidirectional"))
      (node (ref "Y1") (pin "1") (pinfunction "1_1") (pintype "passive"))
    )
    (net (code "51") (name "unconnected-(CON4-Pad6)") (class "Default")
      (node (ref "CON4") (pin "6") (pinfunction "6_6") (pintype "passive"))
    )
    (net (code "52") (name "unconnected-(CON5-Pad1)") (class "Default")
      (node (ref "CON5") (pin "1") (pinfunction "1_1") (pintype "passive"))
    )
    (net (code "53") (name "unconnected-(CON8-Pad1)") (class "Default")
      (node (ref "CON8") (pin "1") (pinfunction "1_1") (pintype "passive"))
    )
    (net (code "54") (name "unconnected-(CON10-Pad1)") (class "Default")
      (node (ref "CON10") (pin "1") (pinfunction "1_1") (pintype "passive"))
    )
    (net (code "55") (name "unconnected-(CON10-Pad2)") (class "Default")
      (node (ref "CON10") (pin "2") (pinfunction "2_2") (pintype "passive"))
    )
    (net (code "56") (name "unconnected-(CON10-Pad7)") (class "Default")
      (node (ref "CON10") (pin "7") (pinfunction "7_7") (pintype "passive"))
    )
    (net (code "57") (name "unconnected-(CON10-Pad8)") (class "Default")
      (node (ref "CON10") (pin "8") (pinfunction "8_8") (pintype "passive"))
    )
    (net (code "58") (name "unconnected-(CON10-SHIELD1-Pad9)") (class "Default")
      (node (ref "CON10") (pin "9") (pinfunction "SHIELD1_9") (pintype "passive"))
    )
    (net (code "59") (name "unconnected-(CON10-SHIELD2-Pad10)") (class "Default")
      (node (ref "CON10") (pin "10") (pinfunction "SHIELD2_10") (pintype "passive"))
    )
    (net (code "60") (name "unconnected-(CON11-Pad1)") (class "Default")
      (node (ref "CON11") (pin "1") (pinfunction "1_1") (pintype "passive"))
    )
    (net (code "61") (name "unconnected-(CON12-Pad1)") (class "Default")
      (node (ref "CON12") (pin "1") (pinfunction "1_1") (pintype "passive"))
    )
    (net (code "62") (name "unconnected-(CON13-Pad1)") (class "Default")
      (node (ref "CON13") (pin "1") (pinfunction "1_1") (pintype "passive"))
    )
    (net (code "63") (name "unconnected-(CON14-Pad1)") (class "Default")
      (node (ref "CON14") (pin "1") (pinfunction "1_1") (pintype "passive"))
    )
    (net (code "64") (name "unconnected-(CON15-Pad1)") (class "Default")
      (node (ref "CON15") (pin "1") (pinfunction "1_1") (pintype "passive"))
    )
    (net (code "65") (name "unconnected-(CON16-Pad1)") (class "Default")
      (node (ref "CON16") (pin "1") (pinfunction "1_1") (pintype "passive"))
    )
    (net (code "66") (name "unconnected-(CON17-Pad1)") (class "Default")
      (node (ref "CON17") (pin "1") (pinfunction "1_1") (pintype "passive"))
    )
    (net (code "67") (name "unconnected-(CON18-Pad1)") (class "Default")
      (node (ref "CON18") (pin "1") (pinfunction "1_1") (pintype "passive"))
    )
    (net (code "68") (name "unconnected-(IC2-2A-Pad7)") (class "Default")
      (node (ref "IC2") (pin "7") (pinfunction "2A_7") (pintype "bidirectional"))
    )
    (net (code "69") (name "unconnected-(IC2-2Y-Pad6)") (class "Default")
      (node (ref "IC2") (pin "6") (pinfunction "2Y_6") (pintype "bidirectional"))
    )
    (net (code "70") (name "unconnected-(IC2-3,4EN-Pad9)") (class "Default")
      (node (ref "IC2") (pin "9") (pinfunction "3,4EN_9") (pintype "bidirectional"))
    )
    (net (code "71") (name "unconnected-(IC2-3A-Pad10)") (class "Default")
      (node (ref "IC2") (pin "10") (pinfunction "3A_10") (pintype "bidirectional"))
    )
    (net (code "72") (name "unconnected-(IC2-3Y-Pad11)") (class "Default")
      (node (ref "IC2") (pin "11") (pinfunction "3Y_11") (pintype "bidirectional"))
    )
    (net (code "73") (name "unconnected-(IC2-4A-Pad15)") (class "Default")
      (node (ref "IC2") (pin "15") (pinfunction "4A_15") (pintype "bidirectional"))
    )
    (net (code "74") (name "unconnected-(IC2-4Y-Pad14)") (class "Default")
      (node (ref "IC2") (pin "14") (pinfunction "4Y_14") (pintype "bidirectional"))
    )
    (net (code "75") (name "unconnected-(IC2-GND2-Pad5)") (class "Default")
      (node (ref "IC2") (pin "5") (pinfunction "GND2_5") (pintype "bidirectional"))
    )
    (net (code "76") (name "unconnected-(IC2-GND3-Pad13)") (class "Default")
      (node (ref "IC2") (pin "13") (pinfunction "GND3_13") (pintype "bidirectional"))
    )
    (net (code "77") (name "unconnected-(IC2-GND4-Pad12)") (class "Default")
      (node (ref "IC2") (pin "12") (pinfunction "GND4_12") (pintype "bidirectional"))
    )
    (net (code "78") (name "unconnected-(IC3-DIN2-Pad10)") (class "Default")
      (node (ref "IC3") (pin "10") (pinfunction "DIN2_10") (pintype "bidirectional"))
    )
    (net (code "79") (name "unconnected-(IC3-DOUT2-Pad7)") (class "Default")
      (node (ref "IC3") (pin "7") (pinfunction "DOUT2_7") (pintype "bidirectional"))
    )
    (net (code "80") (name "unconnected-(IC3-RIN2-Pad8)") (class "Default")
      (node (ref "IC3") (pin "8") (pinfunction "RIN2_8") (pintype "bidirectional"))
    )
    (net (code "81") (name "unconnected-(IC3-ROUT2-Pad9)") (class "Default")
      (node (ref "IC3") (pin "9") (pinfunction "ROUT2_9") (pintype "bidirectional"))
    )
    (net (code "82") (name "unconnected-(IC4-3IN+-Pad10)") (class "Default")
      (node (ref "IC4") (pin "10") (pinfunction "3IN+_10") (pintype "bidirectional"))
    )
    (net (code "83") (name "unconnected-(IC4-3IN--Pad9)") (class "Default")
      (node (ref "IC4") (pin "9") (pinfunction "3IN-_9") (pintype "bidirectional"))
    )
    (net (code "84") (name "unconnected-(IC4-3OUT-Pad8)") (class "Default")
      (node (ref "IC4") (pin "8") (pinfunction "3OUT_8") (pintype "bidirectional"))
    )
    (net (code "85") (name "unconnected-(IC5-3IN+-Pad10)") (class "Default")
      (node (ref "IC5") (pin "10") (pinfunction "3IN+_10") (pintype "bidirectional"))
    )
    (net (code "86") (name "unconnected-(IC5-3IN--Pad9)") (class "Default")
      (node (ref "IC5") (pin "9") (pinfunction "3IN-_9") (pintype "bidirectional"))
    )
    (net (code "87") (name "unconnected-(IC5-3OUT-Pad8)") (class "Default")
      (node (ref "IC5") (pin "8") (pinfunction "3OUT_8") (pintype "bidirectional"))
    )
    (net (code "88") (name "unconnected-(STEERING-WHEEL-Pad5)") (class "Default")
      (node (ref "STEERING-WHEEL") (pin "5") (pinfunction "5_5") (pintype "passive"))
    )
    (net (code "89") (name "unconnected-(STEERING-WHEEL-Pad6)") (class "Default")
      (node (ref "STEERING-WHEEL") (pin "6") (pinfunction "6_6") (pintype "passive"))
    )
    (net (code "90") (name "unconnected-(STEERING-WHEEL-Pad7)") (class "Default")
      (node (ref "STEERING-WHEEL") (pin "7") (pinfunction "7_7") (pintype "passive"))
    )
    (net (code "91") (name "unconnected-(STEERING-WHEEL-Pad8)") (class "Default")
      (node (ref "STEERING-WHEEL") (pin "8") (pinfunction "8_8") (pintype "passive"))
    )
    (net (code "92") (name "unconnected-(UC1-PB3(MOSI{slash}OC2)-Pad17)") (class "Default")
      (node (ref "UC1") (pin "17") (pinfunction "PB3(MOSI/OC2)_17") (pintype "bidirectional"))
    )
    (net (code "93") (name "unconnected-(UC1-PB4(MISO)-Pad18)") (class "Default")
      (node (ref "UC1") (pin "18") (pinfunction "PB4(MISO)_18") (pintype "bidirectional"))
    )
    (net (code "94") (name "unconnected-(UC1-PB5(SCK)-Pad19)") (class "Default")
      (node (ref "UC1") (pin "19") (pinfunction "PB5(SCK)_19") (pintype "bidirectional"))
    )
  )
)
